# M_C_ext_main.net
KiCad netlist of a schematic drawn in EAGLE
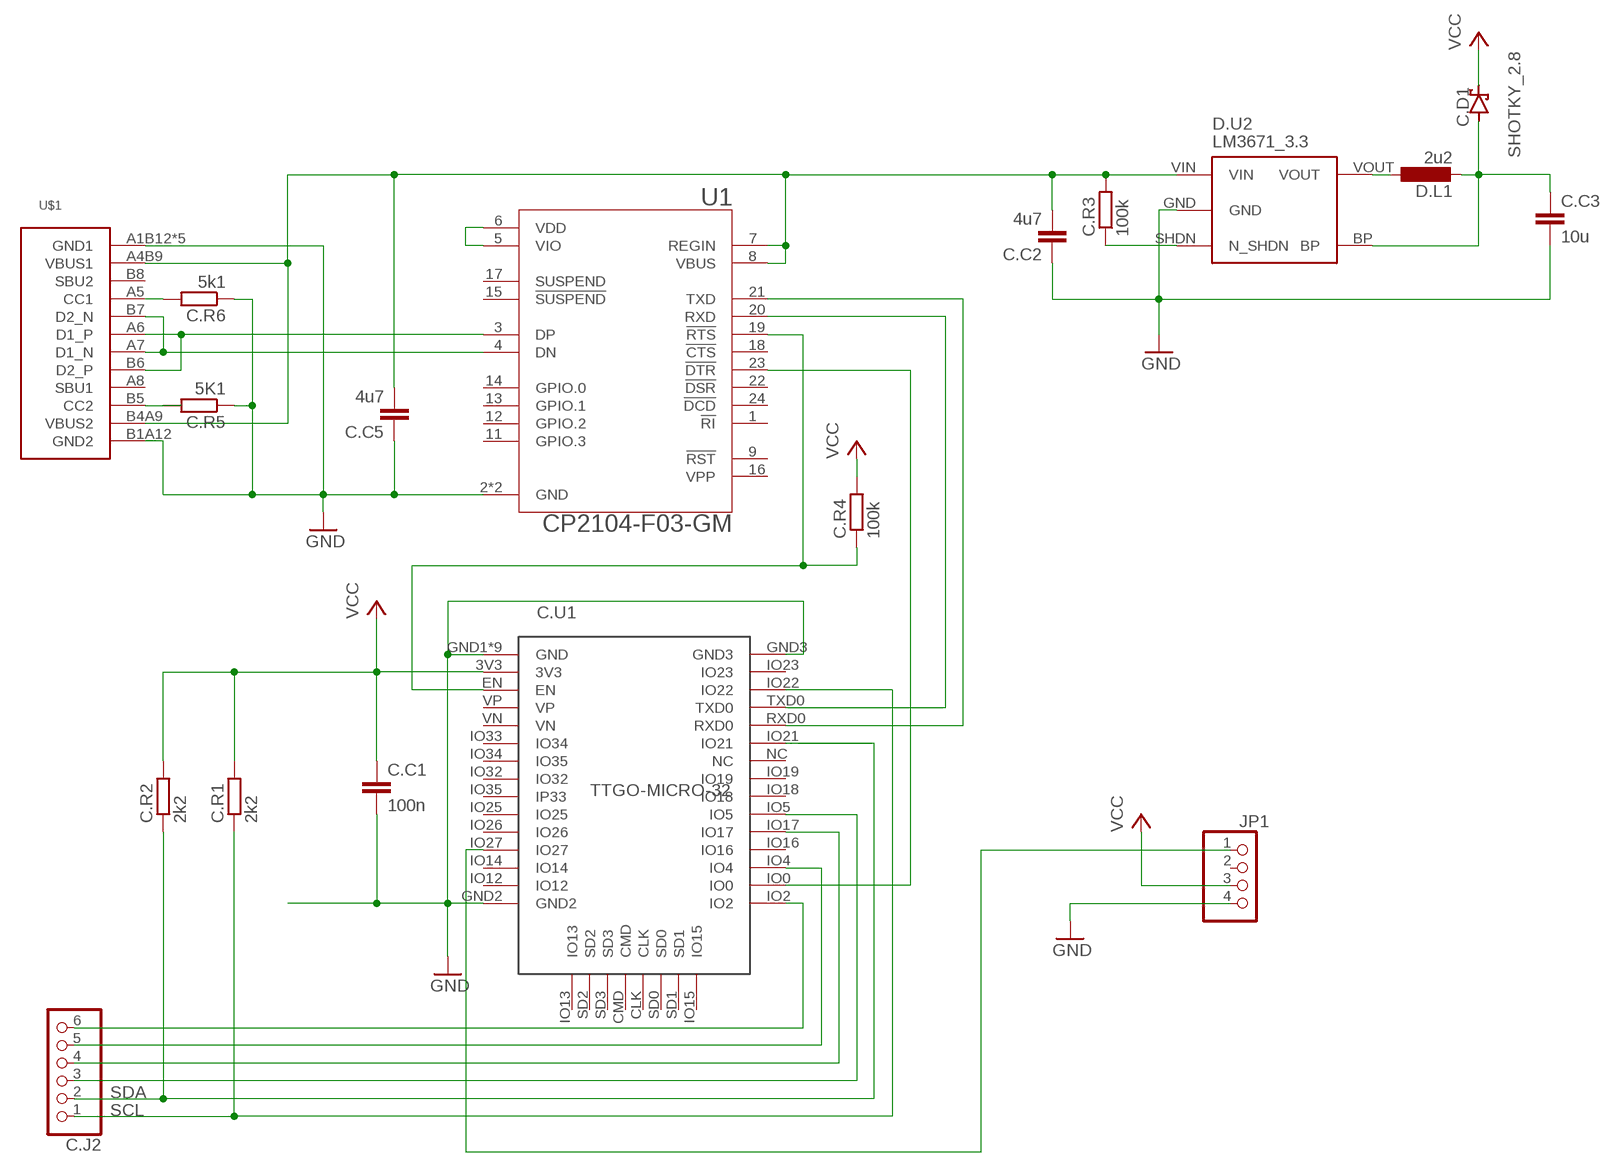
[diagram p0: schematic, sheet 1]

(export (version "E")
  (design (tool "Eeschema 10.0.6"))
  (components
    (comp (ref "C.C1")
      (value "100n")
      (footprint "eagle-import:C0603")
      (libsource (lib "eagle-import") (part "C-EUC0603"))
    )
    (comp (ref "C.C2")
      (value "4u7")
      (footprint "eagle-import:C0603")
      (libsource (lib "eagle-import") (part "C-EUC0603"))
    )
    (comp (ref "C.C3")
      (value "10u")
      (footprint "eagle-import:C0805")
      (libsource (lib "eagle-import") (part "C-EUC0805"))
    )
    (comp (ref "C.C5")
      (value "4u7")
      (footprint "eagle-import:C0603")
      (libsource (lib "eagle-import") (part "C-EUC0603"))
    )
    (comp (ref "C.D1")
      (value "SHOTKY_2.8")
      (footprint "eagle-import:SHOTKY_2.8")
      (libsource (lib "eagle-import") (part "SHOTKY_2.8"))
    )
    (comp (ref "C.J2")
      (value "PINHD-1X6")
      (footprint "eagle-import:1X06")
      (libsource (lib "eagle-import") (part "PINHD-1X6"))
    )
    (comp (ref "C.R1")
      (value "2k2")
      (footprint "eagle-import:R0603")
      (libsource (lib "eagle-import") (part "R-EU_R0603"))
    )
    (comp (ref "C.R2")
      (value "2k2")
      (footprint "eagle-import:R0603")
      (libsource (lib "eagle-import") (part "R-EU_R0603"))
    )
    (comp (ref "C.R3")
      (value "100k")
      (footprint "eagle-import:R0603")
      (libsource (lib "eagle-import") (part "R-EU_R0603"))
    )
    (comp (ref "C.R4")
      (value "100k")
      (footprint "eagle-import:R0603")
      (libsource (lib "eagle-import") (part "R-EU_R0603"))
    )
    (comp (ref "C.R5")
      (value "5K1")
      (footprint "eagle-import:R0603")
      (libsource (lib "eagle-import") (part "R-EU_R0603"))
    )
    (comp (ref "C.R6")
      (value "5k1")
      (footprint "eagle-import:R0603")
      (libsource (lib "eagle-import") (part "R-EU_R0603"))
    )
    (comp (ref "C.U1")
      (value "TTGO-MICRO-32")
      (footprint "eagle-import:TTGO-MICRO-32")
      (libsource (lib "eagle-import") (part "TTGO-MICRO-32"))
    )
    (comp (ref "D.L1")
      (value "2u2")
      (footprint "eagle-import:L3230M")
      (libsource (lib "eagle-import") (part "L-EUL3230M"))
    )
    (comp (ref "D.U2")
      (value "LM3671_3.3")
      (footprint "eagle-import:SOT32-5")
      (libsource (lib "eagle-import") (part "STABILISER_APE8865"))
    )
    (comp (ref "JP1")
      (value "PINHD-1X4")
      (footprint "eagle-import:1X04")
      (libsource (lib "eagle-import") (part "PINHD-1X4"))
    )
    (comp (ref "U$1")
      (value "USB-C")
      (footprint "eagle-import:USB-C")
      (libsource (lib "eagle-import") (part "USB-C"))
    )
    (comp (ref "U1")
      (value "CP2104-F03-GM")
      (footprint "eagle-import:QFN50P400X400X80-25N")
      (fields (field (name "MF") "Silicon Labs") (field (name "MP") "CP2104"))
      (libsource (lib "eagle-import") (part "CP2104-F03-GM"))
    )
  )
  (nets
    (net (code "1") (name "/SCL") (class "Default")
      (node (ref "C.J2") (pin "1") (pinfunction "1_1") (pintype "passive"))
      (node (ref "C.R1") (pin "1") (pinfunction "1_1") (pintype "passive"))
      (node (ref "C.U1") (pin "IO22") (pinfunction "IO22_IO22") (pintype "bidirectional"))
    )
    (net (code "2") (name "/SDA") (class "Default")
      (node (ref "C.J2") (pin "2") (pinfunction "2_2") (pintype "passive"))
      (node (ref "C.R2") (pin "1") (pinfunction "1_1") (pintype "passive"))
      (node (ref "C.U1") (pin "IO21") (pinfunction "IO21_IO21") (pintype "bidirectional"))
    )
    (net (code "3") (name "GND") (class "Default")
      (node (ref "C.C1") (pin "2") (pinfunction "2_2") (pintype "passive"))
      (node (ref "C.C2") (pin "1") (pinfunction "1_1") (pintype "passive"))
      (node (ref "C.C3") (pin "2") (pinfunction "2_2") (pintype "passive"))
      (node (ref "C.C5") (pin "1") (pinfunction "1_1") (pintype "passive"))
      (node (ref "C.R5") (pin "1") (pinfunction "1_1") (pintype "passive"))
      (node (ref "C.R6") (pin "1") (pinfunction "1_1") (pintype "passive"))
      (node (ref "C.U1") (pin "GND1") (pinfunction "GND_GND1") (pintype "power_in"))
      (node (ref "C.U1") (pin "GND10") (pinfunction "GND_GND10") (pintype "power_in"))
      (node (ref "C.U1") (pin "GND11") (pinfunction "GND_GND11") (pintype "power_in"))
      (node (ref "C.U1") (pin "GND2") (pinfunction "GND2_GND2") (pintype "power_in"))
      (node (ref "C.U1") (pin "GND3") (pinfunction "GND3_GND3") (pintype "power_in"))
      (node (ref "C.U1") (pin "GND4") (pinfunction "GND_GND4") (pintype "power_in"))
      (node (ref "C.U1") (pin "GND5") (pinfunction "GND_GND5") (pintype "power_in"))
      (node (ref "C.U1") (pin "GND6") (pinfunction "GND_GND6") (pintype "power_in"))
      (node (ref "C.U1") (pin "GND7") (pinfunction "GND_GND7") (pintype "power_in"))
      (node (ref "C.U1") (pin "GND8") (pinfunction "GND_GND8") (pintype "power_in"))
      (node (ref "C.U1") (pin "GND9") (pinfunction "GND_GND9") (pintype "power_in"))
      (node (ref "D.U2") (pin "GND") (pinfunction "GND_GND") (pintype "bidirectional"))
      (node (ref "JP1") (pin "4") (pinfunction "4_4") (pintype "passive"))
      (node (ref "U$1") (pin "A1B12") (pinfunction "GND1_A1B12") (pintype "bidirectional"))
      (node (ref "U$1") (pin "B1A12") (pinfunction "GND2_B1A12") (pintype "bidirectional"))
      (node (ref "U$1") (pin "SH1") (pinfunction "GND1_SH1") (pintype "bidirectional"))
      (node (ref "U$1") (pin "SH2") (pinfunction "GND1_SH2") (pintype "bidirectional"))
      (node (ref "U$1") (pin "SH3") (pinfunction "GND1_SH3") (pintype "bidirectional"))
      (node (ref "U$1") (pin "SH4") (pinfunction "GND1_SH4") (pintype "bidirectional"))
      (node (ref "U1") (pin "2") (pinfunction "GND_2") (pintype "power_in"))
      (node (ref "U1") (pin "25") (pinfunction "GND_25") (pintype "power_in"))
    )
    (net (code "4") (name "Net-(C.C3-Pad1)") (class "Default")
      (node (ref "C.C3") (pin "1") (pinfunction "1_1") (pintype "passive"))
      (node (ref "C.D1") (pin "A") (pinfunction "A_A") (pintype "passive"))
      (node (ref "D.L1") (pin "2") (pinfunction "2_2") (pintype "passive"))
      (node (ref "D.U2") (pin "BP") (pinfunction "BP_BP") (pintype "bidirectional"))
    )
    (net (code "5") (name "Net-(C.J2-Pad3)") (class "Default")
      (node (ref "C.J2") (pin "3") (pinfunction "3_3") (pintype "passive"))
      (node (ref "C.U1") (pin "IO5") (pinfunction "IO5_IO5") (pintype "bidirectional"))
    )
    (net (code "6") (name "Net-(C.J2-Pad4)") (class "Default")
      (node (ref "C.J2") (pin "4") (pinfunction "4_4") (pintype "passive"))
      (node (ref "C.U1") (pin "IO17") (pinfunction "IO17_IO17") (pintype "bidirectional"))
    )
    (net (code "7") (name "Net-(C.J2-Pad5)") (class "Default")
      (node (ref "C.J2") (pin "5") (pinfunction "5_5") (pintype "passive"))
      (node (ref "C.U1") (pin "IO4") (pinfunction "IO4_IO4") (pintype "bidirectional"))
    )
    (net (code "8") (name "Net-(C.J2-Pad6)") (class "Default")
      (node (ref "C.J2") (pin "6") (pinfunction "6_6") (pintype "passive"))
      (node (ref "C.U1") (pin "IO2") (pinfunction "IO2_IO2") (pintype "bidirectional"))
    )
    (net (code "9") (name "Net-(C.U1-PadIO27)") (class "Default")
      (node (ref "C.U1") (pin "IO27") (pinfunction "IO27_IO27") (pintype "bidirectional"))
      (node (ref "JP1") (pin "1") (pinfunction "1_1") (pintype "passive"))
    )
    (net (code "10") (name "Net-(D.L1-Pad1)") (class "Default")
      (node (ref "D.L1") (pin "1") (pinfunction "1_1") (pintype "passive"))
      (node (ref "D.U2") (pin "VOUT") (pinfunction "VOUT_VOUT") (pintype "bidirectional"))
    )
    (net (code "11") (name "Net-(D.U2-N_SHDN)") (class "Default")
      (node (ref "C.R3") (pin "1") (pinfunction "1_1") (pintype "passive"))
      (node (ref "D.U2") (pin "SHDN") (pinfunction "N_SHDN_SHDN") (pintype "bidirectional"))
    )
    (net (code "12") (name "Net-(U$1-CC1)") (class "Default")
      (node (ref "C.R6") (pin "2") (pinfunction "2_2") (pintype "passive"))
      (node (ref "U$1") (pin "A5") (pinfunction "CC1_A5") (pintype "bidirectional"))
    )
    (net (code "13") (name "Net-(U$1-CC2)") (class "Default")
      (node (ref "C.R5") (pin "2") (pinfunction "2_2") (pintype "passive"))
      (node (ref "U$1") (pin "B5") (pinfunction "CC2_B5") (pintype "bidirectional"))
    )
    (net (code "14") (name "Net-(U$1-D1_N)") (class "Default")
      (node (ref "U$1") (pin "A7") (pinfunction "D1_N_A7") (pintype "bidirectional"))
      (node (ref "U$1") (pin "B7") (pinfunction "D2_N_B7") (pintype "bidirectional"))
      (node (ref "U1") (pin "4") (pinfunction "DN_4") (pintype "bidirectional"))
    )
    (net (code "15") (name "Net-(U$1-D1_P)") (class "Default")
      (node (ref "U$1") (pin "A6") (pinfunction "D1_P_A6") (pintype "bidirectional"))
      (node (ref "U$1") (pin "B6") (pinfunction "D2_P_B6") (pintype "bidirectional"))
      (node (ref "U1") (pin "3") (pinfunction "DP_3") (pintype "bidirectional"))
    )
    (net (code "16") (name "Net-(U$1-VBUS1)") (class "Default")
      (node (ref "C.C2") (pin "2") (pinfunction "2_2") (pintype "passive"))
      (node (ref "C.C5") (pin "2") (pinfunction "2_2") (pintype "passive"))
      (node (ref "C.R3") (pin "2") (pinfunction "2_2") (pintype "passive"))
      (node (ref "D.U2") (pin "VIN") (pinfunction "VIN_VIN") (pintype "bidirectional"))
      (node (ref "U$1") (pin "A4B9") (pinfunction "VBUS1_A4B9") (pintype "bidirectional"))
      (node (ref "U$1") (pin "B4A9") (pinfunction "VBUS2_B4A9") (pintype "bidirectional"))
      (node (ref "U1") (pin "7") (pinfunction "REGIN_7") (pintype "input"))
      (node (ref "U1") (pin "8") (pinfunction "VBUS_8") (pintype "input"))
    )
    (net (code "17") (name "Net-(U1-RXD)") (class "Default")
      (node (ref "C.U1") (pin "TXD0") (pinfunction "TXD0_TXD0") (pintype "bidirectional"))
      (node (ref "U1") (pin "20") (pinfunction "RXD_20") (pintype "input"))
    )
    (net (code "18") (name "Net-(U1-TXD)") (class "Default")
      (node (ref "C.U1") (pin "RXD0") (pinfunction "RXD0_RXD0") (pintype "bidirectional"))
      (node (ref "U1") (pin "21") (pinfunction "TXD_21") (pintype "output"))
    )
    (net (code "19") (name "Net-(U1-VDD)") (class "Default")
      (node (ref "U1") (pin "5") (pinfunction "VIO_5") (pintype "power_in"))
      (node (ref "U1") (pin "6") (pinfunction "VDD_6") (pintype "power_in"))
    )
    (net (code "20") (name "Net-(U1-~{DTR})") (class "Default")
      (node (ref "C.U1") (pin "IO0") (pinfunction "IO0_IO0") (pintype "bidirectional"))
      (node (ref "U1") (pin "23") (pinfunction "~{DTR}_23") (pintype "output"))
    )
    (net (code "21") (name "Net-(U1-~{RTS})") (class "Default")
      (node (ref "C.R4") (pin "1") (pinfunction "1_1") (pintype "passive"))
      (node (ref "C.U1") (pin "EN") (pinfunction "EN_EN") (pintype "bidirectional"))
      (node (ref "U1") (pin "19") (pinfunction "~{RTS}_19") (pintype "output"))
    )
    (net (code "22") (name "VCC") (class "Default")
      (node (ref "C.C1") (pin "1") (pinfunction "1_1") (pintype "passive"))
      (node (ref "C.D1") (pin "K") (pinfunction "C_K") (pintype "passive"))
      (node (ref "C.R1") (pin "2") (pinfunction "2_2") (pintype "passive"))
      (node (ref "C.R2") (pin "2") (pinfunction "2_2") (pintype "passive"))
      (node (ref "C.R4") (pin "2") (pinfunction "2_2") (pintype "passive"))
      (node (ref "C.U1") (pin "3V3") (pinfunction "3V3_3V3") (pintype "power_in"))
      (node (ref "JP1") (pin "3") (pinfunction "3_3") (pintype "passive"))
    )
    (net (code "23") (name "unconnected-(C.U1-IO34-PadIO33)") (class "Default")
      (node (ref "C.U1") (pin "IO33") (pinfunction "IO34_IO33") (pintype "bidirectional"))
    )
    (net (code "24") (name "unconnected-(C.U1-IO35-PadIO34)") (class "Default")
      (node (ref "C.U1") (pin "IO34") (pinfunction "IO35_IO34") (pintype "bidirectional"))
    )
    (net (code "25") (name "unconnected-(C.U1-IP33-PadIO35)") (class "Default")
      (node (ref "C.U1") (pin "IO35") (pinfunction "IP33_IO35") (pintype "bidirectional"))
    )
    (net (code "26") (name "unconnected-(C.U1-PadCLK)") (class "Default")
      (node (ref "C.U1") (pin "CLK") (pinfunction "CLK_CLK") (pintype "bidirectional"))
    )
    (net (code "27") (name "unconnected-(C.U1-PadCMD)") (class "Default")
      (node (ref "C.U1") (pin "CMD") (pinfunction "CMD_CMD") (pintype "bidirectional"))
    )
    (net (code "28") (name "unconnected-(C.U1-PadIO12)") (class "Default")
      (node (ref "C.U1") (pin "IO12") (pinfunction "IO12_IO12") (pintype "bidirectional"))
    )
    (net (code "29") (name "unconnected-(C.U1-PadIO13)") (class "Default")
      (node (ref "C.U1") (pin "IO13") (pinfunction "IO13_IO13") (pintype "bidirectional"))
    )
    (net (code "30") (name "unconnected-(C.U1-PadIO14)") (class "Default")
      (node (ref "C.U1") (pin "IO14") (pinfunction "IO14_IO14") (pintype "bidirectional"))
    )
    (net (code "31") (name "unconnected-(C.U1-PadIO15)") (class "Default")
      (node (ref "C.U1") (pin "IO15") (pinfunction "IO15_IO15") (pintype "bidirectional"))
    )
    (net (code "32") (name "unconnected-(C.U1-PadIO16)") (class "Default")
      (node (ref "C.U1") (pin "IO16") (pinfunction "IO16_IO16") (pintype "bidirectional"))
    )
    (net (code "33") (name "unconnected-(C.U1-PadIO18)") (class "Default")
      (node (ref "C.U1") (pin "IO18") (pinfunction "IO18_IO18") (pintype "bidirectional"))
    )
    (net (code "34") (name "unconnected-(C.U1-PadIO19)") (class "Default")
      (node (ref "C.U1") (pin "IO19") (pinfunction "IO19_IO19") (pintype "bidirectional"))
    )
    (net (code "35") (name "unconnected-(C.U1-PadIO23)") (class "Default")
      (node (ref "C.U1") (pin "IO23") (pinfunction "IO23_IO23") (pintype "bidirectional"))
    )
    (net (code "36") (name "unconnected-(C.U1-PadIO25)") (class "Default")
      (node (ref "C.U1") (pin "IO25") (pinfunction "IO25_IO25") (pintype "bidirectional"))
    )
    (net (code "37") (name "unconnected-(C.U1-PadIO26)") (class "Default")
      (node (ref "C.U1") (pin "IO26") (pinfunction "IO26_IO26") (pintype "bidirectional"))
    )
    (net (code "38") (name "unconnected-(C.U1-PadIO32)") (class "Default")
      (node (ref "C.U1") (pin "IO32") (pinfunction "IO32_IO32") (pintype "bidirectional"))
    )
    (net (code "39") (name "unconnected-(C.U1-PadNC)") (class "Default")
      (node (ref "C.U1") (pin "NC") (pinfunction "NC_NC") (pintype "no_connect"))
    )
    (net (code "40") (name "unconnected-(C.U1-PadSD0)") (class "Default")
      (node (ref "C.U1") (pin "SD0") (pinfunction "SD0_SD0") (pintype "bidirectional"))
    )
    (net (code "41") (name "unconnected-(C.U1-PadSD1)") (class "Default")
      (node (ref "C.U1") (pin "SD1") (pinfunction "SD1_SD1") (pintype "bidirectional"))
    )
    (net (code "42") (name "unconnected-(C.U1-PadSD2)") (class "Default")
      (node (ref "C.U1") (pin "SD2") (pinfunction "SD2_SD2") (pintype "bidirectional"))
    )
    (net (code "43") (name "unconnected-(C.U1-PadSD3)") (class "Default")
      (node (ref "C.U1") (pin "SD3") (pinfunction "SD3_SD3") (pintype "bidirectional"))
    )
    (net (code "44") (name "unconnected-(C.U1-PadVN)") (class "Default")
      (node (ref "C.U1") (pin "VN") (pinfunction "VN_VN") (pintype "bidirectional"))
    )
    (net (code "45") (name "unconnected-(C.U1-PadVP)") (class "Default")
      (node (ref "C.U1") (pin "VP") (pinfunction "VP_VP") (pintype "bidirectional"))
    )
    (net (code "46") (name "unconnected-(JP1-Pad2)") (class "Default")
      (node (ref "JP1") (pin "2") (pinfunction "2_2") (pintype "passive"))
    )
    (net (code "47") (name "unconnected-(U$1-SBU1-PadA8)") (class "Default")
      (node (ref "U$1") (pin "A8") (pinfunction "SBU1_A8") (pintype "bidirectional"))
    )
    (net (code "48") (name "unconnected-(U$1-SBU2-PadB8)") (class "Default")
      (node (ref "U$1") (pin "B8") (pinfunction "SBU2_B8") (pintype "bidirectional"))
    )
    (net (code "49") (name "unconnected-(U1-GPIO.0-Pad14)") (class "Default")
      (node (ref "U1") (pin "14") (pinfunction "GPIO.0_14") (pintype "bidirectional"))
    )
    (net (code "50") (name "unconnected-(U1-GPIO.1-Pad13)") (class "Default")
      (node (ref "U1") (pin "13") (pinfunction "GPIO.1_13") (pintype "bidirectional"))
    )
    (net (code "51") (name "unconnected-(U1-GPIO.2-Pad12)") (class "Default")
      (node (ref "U1") (pin "12") (pinfunction "GPIO.2_12") (pintype "bidirectional"))
    )
    (net (code "52") (name "unconnected-(U1-GPIO.3-Pad11)") (class "Default")
      (node (ref "U1") (pin "11") (pinfunction "GPIO.3_11") (pintype "bidirectional"))
    )
    (net (code "53") (name "unconnected-(U1-SUSPEND-Pad17)") (class "Default")
      (node (ref "U1") (pin "17") (pinfunction "SUSPEND_17") (pintype "output"))
    )
    (net (code "54") (name "unconnected-(U1-VPP-Pad16)") (class "Default")
      (node (ref "U1") (pin "16") (pinfunction "VPP_16") (pintype "passive"))
    )
    (net (code "55") (name "unconnected-(U1-~{CTS}-Pad18)") (class "Default")
      (node (ref "U1") (pin "18") (pinfunction "~{CTS}_18") (pintype "input"))
    )
    (net (code "56") (name "unconnected-(U1-~{DCD}-Pad24)") (class "Default")
      (node (ref "U1") (pin "24") (pinfunction "~{DCD}_24") (pintype "input"))
    )
    (net (code "57") (name "unconnected-(U1-~{DSR}-Pad22)") (class "Default")
      (node (ref "U1") (pin "22") (pinfunction "~{DSR}_22") (pintype "input"))
    )
    (net (code "58") (name "unconnected-(U1-~{RI}-Pad1)") (class "Default")
      (node (ref "U1") (pin "1") (pinfunction "~{RI}_1") (pintype "input"))
    )
    (net (code "59") (name "unconnected-(U1-~{RST}-Pad9)") (class "Default")
      (node (ref "U1") (pin "9") (pinfunction "~{RST}_9") (pintype "bidirectional"))
    )
    (net (code "60") (name "unconnected-(U1-~{SUSPEND}-Pad15)") (class "Default")
      (node (ref "U1") (pin "15") (pinfunction "~{SUSPEND}_15") (pintype "output"))
    )
  )
)
